# leds-circle.net
KiCad netlist of a schematic drawn in EAGLE
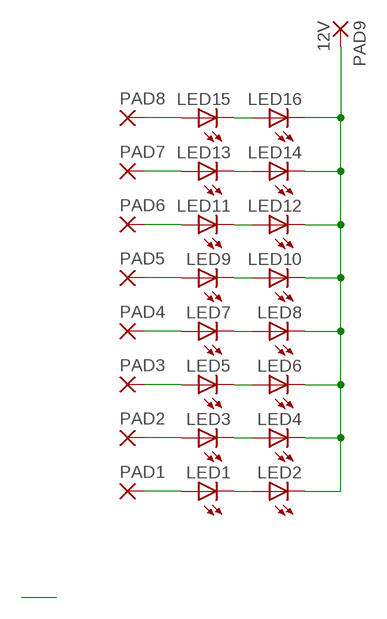
[diagram p0: schematic, sheet 1]

(export (version "E")
  (design (tool "Eeschema 10.0.6"))
  (components
    (comp (ref "LED1")
      (value "LED-FKIT-1206")
      (footprint "eagle-import:FKIT-LED-1206")
      (libsource (lib "eagle-import") (part "LED-FKIT-1206"))
    )
    (comp (ref "LED2")
      (value "LED-FKIT-1206")
      (footprint "eagle-import:FKIT-LED-1206")
      (libsource (lib "eagle-import") (part "LED-FKIT-1206"))
    )
    (comp (ref "LED3")
      (value "LED-FKIT-1206")
      (footprint "eagle-import:FKIT-LED-1206")
      (libsource (lib "eagle-import") (part "LED-FKIT-1206"))
    )
    (comp (ref "LED4")
      (value "LED-FKIT-1206")
      (footprint "eagle-import:FKIT-LED-1206")
      (libsource (lib "eagle-import") (part "LED-FKIT-1206"))
    )
    (comp (ref "LED5")
      (value "LED-FKIT-1206")
      (footprint "eagle-import:FKIT-LED-1206")
      (libsource (lib "eagle-import") (part "LED-FKIT-1206"))
    )
    (comp (ref "LED6")
      (value "LED-FKIT-1206")
      (footprint "eagle-import:FKIT-LED-1206")
      (libsource (lib "eagle-import") (part "LED-FKIT-1206"))
    )
    (comp (ref "LED7")
      (value "LED-FKIT-1206")
      (footprint "eagle-import:FKIT-LED-1206")
      (libsource (lib "eagle-import") (part "LED-FKIT-1206"))
    )
    (comp (ref "LED8")
      (value "LED-FKIT-1206")
      (footprint "eagle-import:FKIT-LED-1206")
      (libsource (lib "eagle-import") (part "LED-FKIT-1206"))
    )
    (comp (ref "LED9")
      (value "LED-FKIT-1206")
      (footprint "eagle-import:FKIT-LED-1206")
      (libsource (lib "eagle-import") (part "LED-FKIT-1206"))
    )
    (comp (ref "LED10")
      (value "LED-FKIT-1206")
      (footprint "eagle-import:FKIT-LED-1206")
      (libsource (lib "eagle-import") (part "LED-FKIT-1206"))
    )
    (comp (ref "LED11")
      (value "LED-FKIT-1206")
      (footprint "eagle-import:FKIT-LED-1206")
      (libsource (lib "eagle-import") (part "LED-FKIT-1206"))
    )
    (comp (ref "LED12")
      (value "LED-FKIT-1206")
      (footprint "eagle-import:FKIT-LED-1206")
      (libsource (lib "eagle-import") (part "LED-FKIT-1206"))
    )
    (comp (ref "LED13")
      (value "LED-FKIT-1206")
      (footprint "eagle-import:FKIT-LED-1206")
      (libsource (lib "eagle-import") (part "LED-FKIT-1206"))
    )
    (comp (ref "LED14")
      (value "LED-FKIT-1206")
      (footprint "eagle-import:FKIT-LED-1206")
      (libsource (lib "eagle-import") (part "LED-FKIT-1206"))
    )
    (comp (ref "LED15")
      (value "LED-FKIT-1206")
      (footprint "eagle-import:FKIT-LED-1206")
      (libsource (lib "eagle-import") (part "LED-FKIT-1206"))
    )
    (comp (ref "LED16")
      (value "LED-FKIT-1206")
      (footprint "eagle-import:FKIT-LED-1206")
      (libsource (lib "eagle-import") (part "LED-FKIT-1206"))
    )
    (comp (ref "PAD1")
      (value "SMD2")
      (footprint "eagle-import:SMD1,27-2,54")
      (libsource (lib "eagle-import") (part "SMD2"))
    )
    (comp (ref "PAD2")
      (value "SMD2")
      (footprint "eagle-import:SMD1,27-2,54")
      (libsource (lib "eagle-import") (part "SMD2"))
    )
    (comp (ref "PAD3")
      (value "SMD2")
      (footprint "eagle-import:SMD1,27-2,54")
      (libsource (lib "eagle-import") (part "SMD2"))
    )
    (comp (ref "PAD4")
      (value "SMD2")
      (footprint "eagle-import:SMD1,27-2,54")
      (libsource (lib "eagle-import") (part "SMD2"))
    )
    (comp (ref "PAD5")
      (value "SMD2")
      (footprint "eagle-import:SMD1,27-2,54")
      (libsource (lib "eagle-import") (part "SMD2"))
    )
    (comp (ref "PAD6")
      (value "SMD2")
      (footprint "eagle-import:SMD1,27-2,54")
      (libsource (lib "eagle-import") (part "SMD2"))
    )
    (comp (ref "PAD7")
      (value "SMD2")
      (footprint "eagle-import:SMD1,27-2,54")
      (libsource (lib "eagle-import") (part "SMD2"))
    )
    (comp (ref "PAD8")
      (value "SMD2")
      (footprint "eagle-import:SMD1,27-2,54")
      (libsource (lib "eagle-import") (part "SMD2"))
    )
    (comp (ref "PAD9")
      (value "12V")
      (footprint "eagle-import:SMD1,27-2,54")
      (libsource (lib "eagle-import") (part "SMD2"))
    )
  )
  (nets
    (net (code "1") (name "Net-(LED1-PadC)") (class "Default")
      (node (ref "LED1") (pin "C") (pinfunction "C_C") (pintype "passive"))
      (node (ref "LED2") (pin "A") (pinfunction "A_A") (pintype "passive"))
    )
    (net (code "2") (name "Net-(LED3-PadC)") (class "Default")
      (node (ref "LED3") (pin "C") (pinfunction "C_C") (pintype "passive"))
      (node (ref "LED4") (pin "A") (pinfunction "A_A") (pintype "passive"))
    )
    (net (code "3") (name "Net-(LED5-PadC)") (class "Default")
      (node (ref "LED5") (pin "C") (pinfunction "C_C") (pintype "passive"))
      (node (ref "LED6") (pin "A") (pinfunction "A_A") (pintype "passive"))
    )
    (net (code "4") (name "Net-(LED7-PadC)") (class "Default")
      (node (ref "LED7") (pin "C") (pinfunction "C_C") (pintype "passive"))
      (node (ref "LED8") (pin "A") (pinfunction "A_A") (pintype "passive"))
    )
    (net (code "5") (name "Net-(LED10-PadA)") (class "Default")
      (node (ref "LED10") (pin "A") (pinfunction "A_A") (pintype "passive"))
      (node (ref "LED9") (pin "C") (pinfunction "C_C") (pintype "passive"))
    )
    (net (code "6") (name "Net-(LED11-PadC)") (class "Default")
      (node (ref "LED11") (pin "C") (pinfunction "C_C") (pintype "passive"))
      (node (ref "LED12") (pin "A") (pinfunction "A_A") (pintype "passive"))
    )
    (net (code "7") (name "Net-(LED13-PadC)") (class "Default")
      (node (ref "LED13") (pin "C") (pinfunction "C_C") (pintype "passive"))
      (node (ref "LED14") (pin "A") (pinfunction "A_A") (pintype "passive"))
    )
    (net (code "8") (name "Net-(LED15-PadC)") (class "Default")
      (node (ref "LED15") (pin "C") (pinfunction "C_C") (pintype "passive"))
      (node (ref "LED16") (pin "A") (pinfunction "A_A") (pintype "passive"))
    )
    (net (code "9") (name "Net-(PAD1-P)") (class "Default")
      (node (ref "LED1") (pin "A") (pinfunction "A_A") (pintype "passive"))
      (node (ref "PAD1") (pin "1") (pinfunction "P_1") (pintype "passive"))
    )
    (net (code "10") (name "Net-(PAD2-P)") (class "Default")
      (node (ref "LED3") (pin "A") (pinfunction "A_A") (pintype "passive"))
      (node (ref "PAD2") (pin "1") (pinfunction "P_1") (pintype "passive"))
    )
    (net (code "11") (name "Net-(PAD3-P)") (class "Default")
      (node (ref "LED5") (pin "A") (pinfunction "A_A") (pintype "passive"))
      (node (ref "PAD3") (pin "1") (pinfunction "P_1") (pintype "passive"))
    )
    (net (code "12") (name "Net-(PAD4-P)") (class "Default")
      (node (ref "LED7") (pin "A") (pinfunction "A_A") (pintype "passive"))
      (node (ref "PAD4") (pin "1") (pinfunction "P_1") (pintype "passive"))
    )
    (net (code "13") (name "Net-(PAD5-P)") (class "Default")
      (node (ref "LED9") (pin "A") (pinfunction "A_A") (pintype "passive"))
      (node (ref "PAD5") (pin "1") (pinfunction "P_1") (pintype "passive"))
    )
    (net (code "14") (name "Net-(PAD6-P)") (class "Default")
      (node (ref "LED11") (pin "A") (pinfunction "A_A") (pintype "passive"))
      (node (ref "PAD6") (pin "1") (pinfunction "P_1") (pintype "passive"))
    )
    (net (code "15") (name "Net-(PAD7-P)") (class "Default")
      (node (ref "LED13") (pin "A") (pinfunction "A_A") (pintype "passive"))
      (node (ref "PAD7") (pin "1") (pinfunction "P_1") (pintype "passive"))
    )
    (net (code "16") (name "Net-(PAD8-P)") (class "Default")
      (node (ref "LED15") (pin "A") (pinfunction "A_A") (pintype "passive"))
      (node (ref "PAD8") (pin "1") (pinfunction "P_1") (pintype "passive"))
    )
    (net (code "17") (name "Net-(PAD9-P)") (class "Default")
      (node (ref "LED10") (pin "C") (pinfunction "C_C") (pintype "passive"))
      (node (ref "LED12") (pin "C") (pinfunction "C_C") (pintype "passive"))
      (node (ref "LED14") (pin "C") (pinfunction "C_C") (pintype "passive"))
      (node (ref "LED16") (pin "C") (pinfunction "C_C") (pintype "passive"))
      (node (ref "LED2") (pin "C") (pinfunction "C_C") (pintype "passive"))
      (node (ref "LED4") (pin "C") (pinfunction "C_C") (pintype "passive"))
      (node (ref "LED6") (pin "C") (pinfunction "C_C") (pintype "passive"))
      (node (ref "LED8") (pin "C") (pinfunction "C_C") (pintype "passive"))
      (node (ref "PAD9") (pin "1") (pinfunction "P_1") (pintype "passive"))
    )
  )
)
